# pwm-control.net
KiCad netlist of a schematic drawn in EAGLE
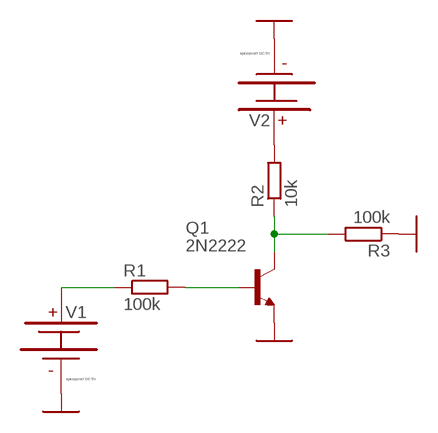
[diagram p0: schematic, sheet 1]

(export (version "E")
  (design (tool "Eeschema 10.0.6"))
  (components
    (comp (ref "Q1")
      (value "2N2222")
      (footprint "eagle-import:TO92-EBC-OVAL")
      (libsource (lib "eagle-import") (part "2N2222"))
    )
    (comp (ref "R1")
      (value "100k")
      (footprint "eagle-import:0204V")
      (libsource (lib "eagle-import") (part "R-EU_0204/2V"))
    )
    (comp (ref "R2")
      (value "10k")
      (footprint "eagle-import:0204V")
      (libsource (lib "eagle-import") (part "R-EU_0204/2V"))
    )
    (comp (ref "R3")
      (value "100k")
      (footprint "eagle-import:0204V")
      (libsource (lib "eagle-import") (part "R-EU_0204/2V"))
    )
    (comp (ref "V1")
      (value "VSOURCE")
      (footprint "eagle-import:VSOURCE")
      (libsource (lib "eagle-import") (part "VSOURCE"))
    )
    (comp (ref "V2")
      (value "VSOURCE")
      (footprint "eagle-import:VSOURCE")
      (libsource (lib "eagle-import") (part "VSOURCE"))
    )
  )
  (nets
    (net (code "1") (name "GND") (class "Default")
      (node (ref "Q1") (pin "E") (pinfunction "E_E") (pintype "passive"))
      (node (ref "R3") (pin "1") (pinfunction "1_1") (pintype "passive"))
      (node (ref "V1") (pin "2") (pinfunction "2_2") (pintype "output"))
      (node (ref "V2") (pin "2") (pinfunction "2_2") (pintype "output"))
    )
    (net (code "2") (name "Net-(Q1-PadB)") (class "Default")
      (node (ref "Q1") (pin "B") (pinfunction "B_B") (pintype "passive"))
      (node (ref "R1") (pin "2") (pinfunction "2_2") (pintype "passive"))
    )
    (net (code "3") (name "Net-(Q1-PadC)") (class "Default")
      (node (ref "Q1") (pin "C") (pinfunction "C_C") (pintype "passive"))
      (node (ref "R2") (pin "1") (pinfunction "1_1") (pintype "passive"))
      (node (ref "R3") (pin "2") (pinfunction "2_2") (pintype "passive"))
    )
    (net (code "4") (name "Net-(R1-Pad1)") (class "Default")
      (node (ref "R1") (pin "1") (pinfunction "1_1") (pintype "passive"))
      (node (ref "V1") (pin "1") (pinfunction "1_1") (pintype "output"))
    )
    (net (code "5") (name "Net-(R2-Pad2)") (class "Default")
      (node (ref "R2") (pin "2") (pinfunction "2_2") (pintype "passive"))
      (node (ref "V2") (pin "1") (pinfunction "1_1") (pintype "output"))
    )
  )
)
